# Rx_V2-2.net
KiCad netlist of a schematic drawn in EAGLE
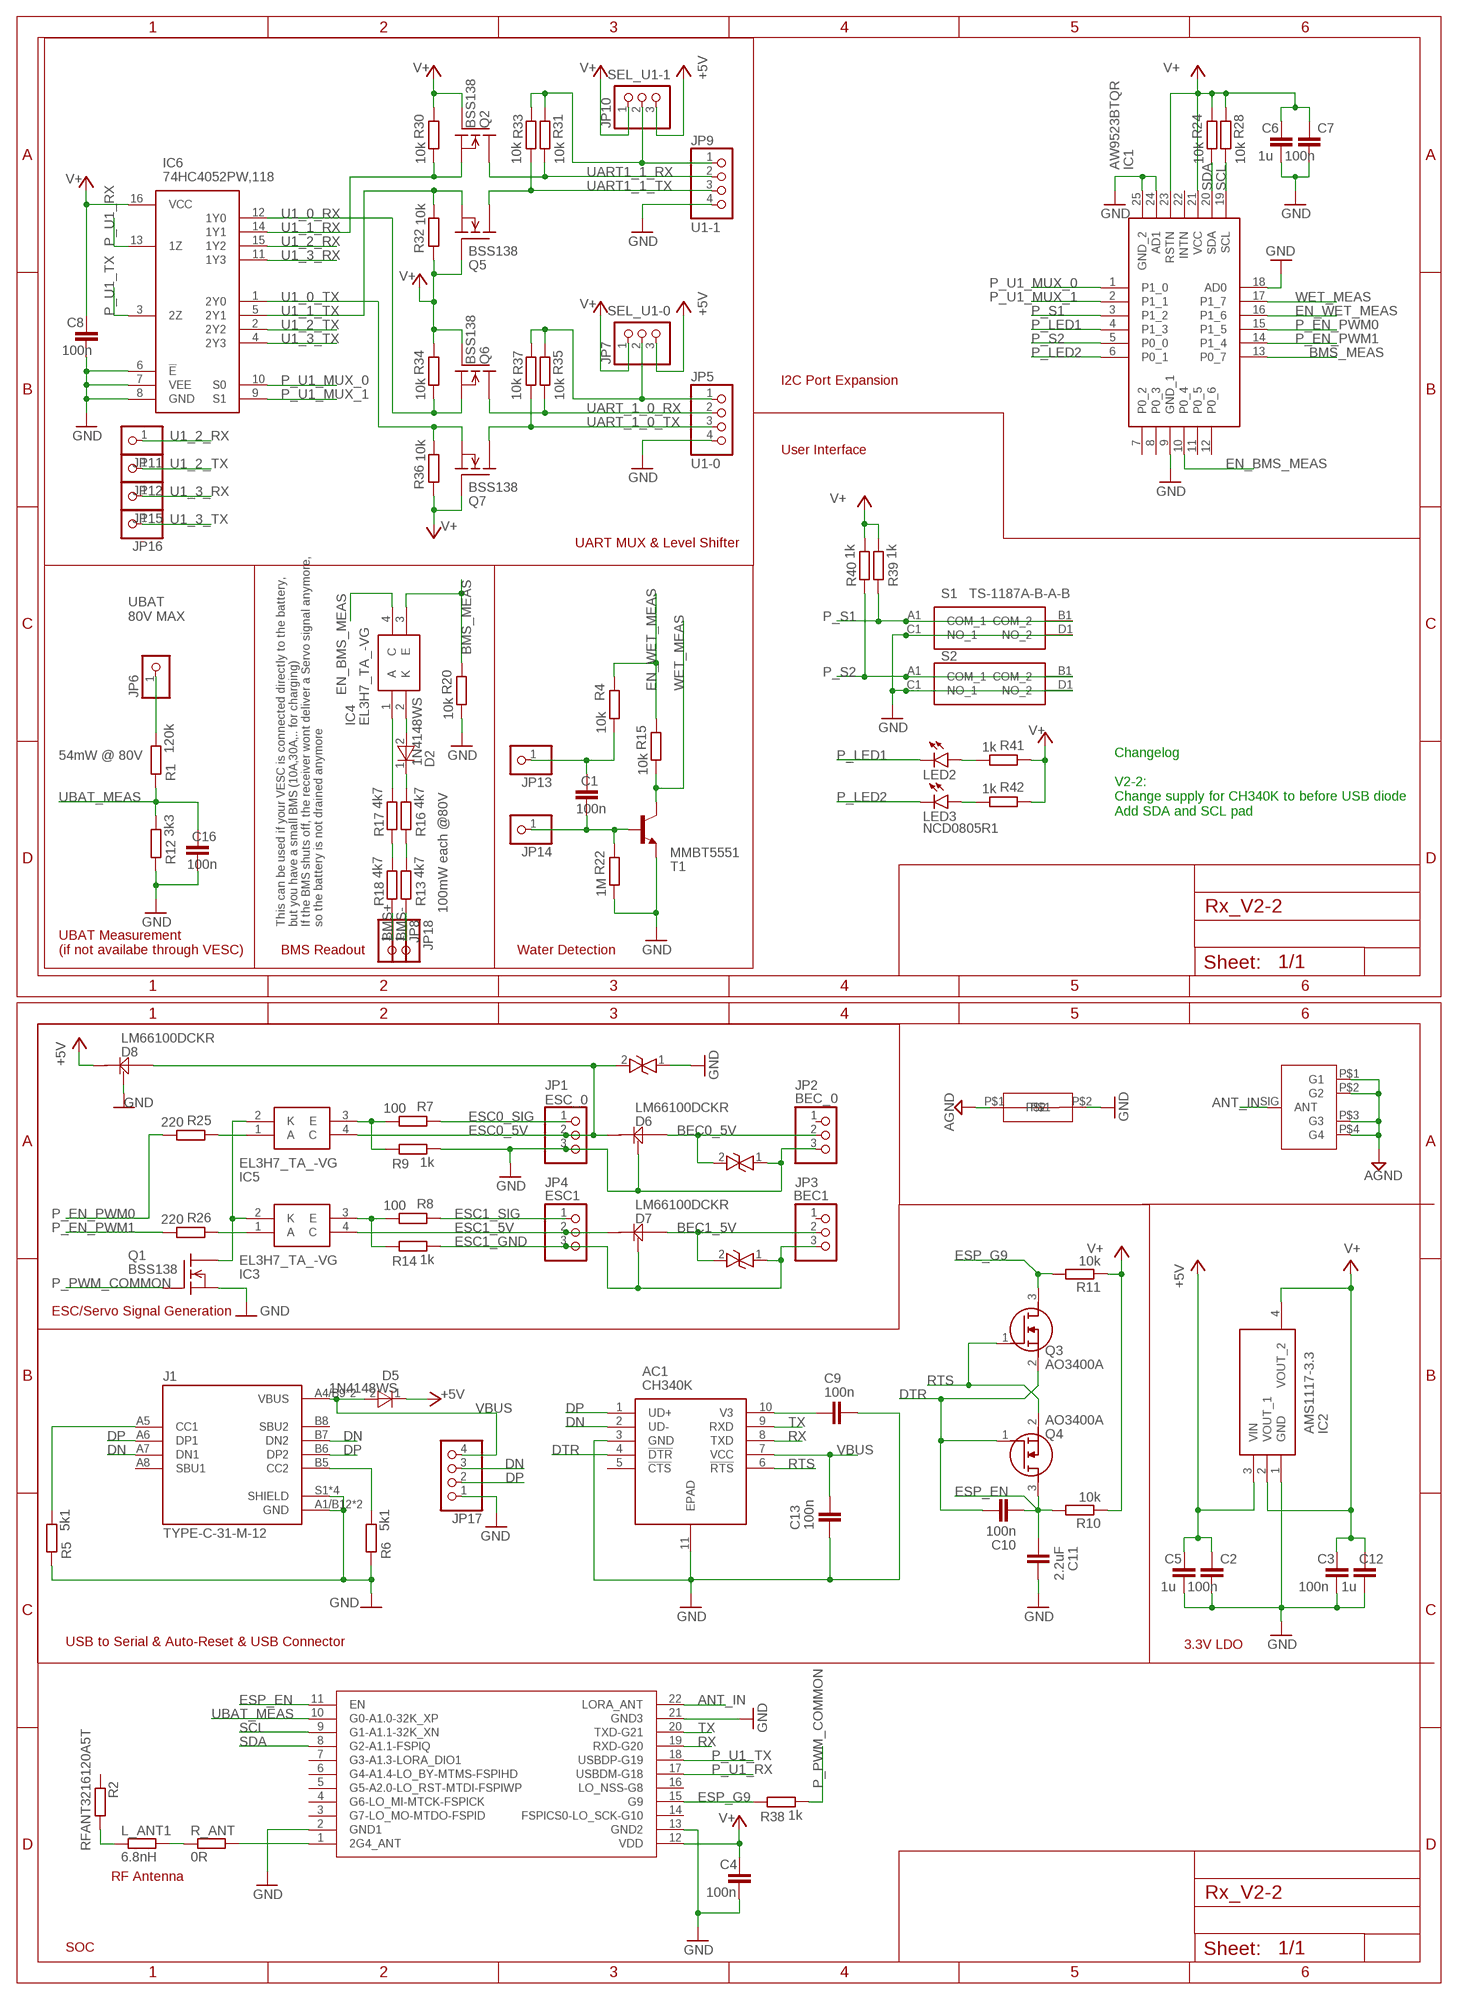
[diagram p0: schematic, sheet 1, part 1 of 2]
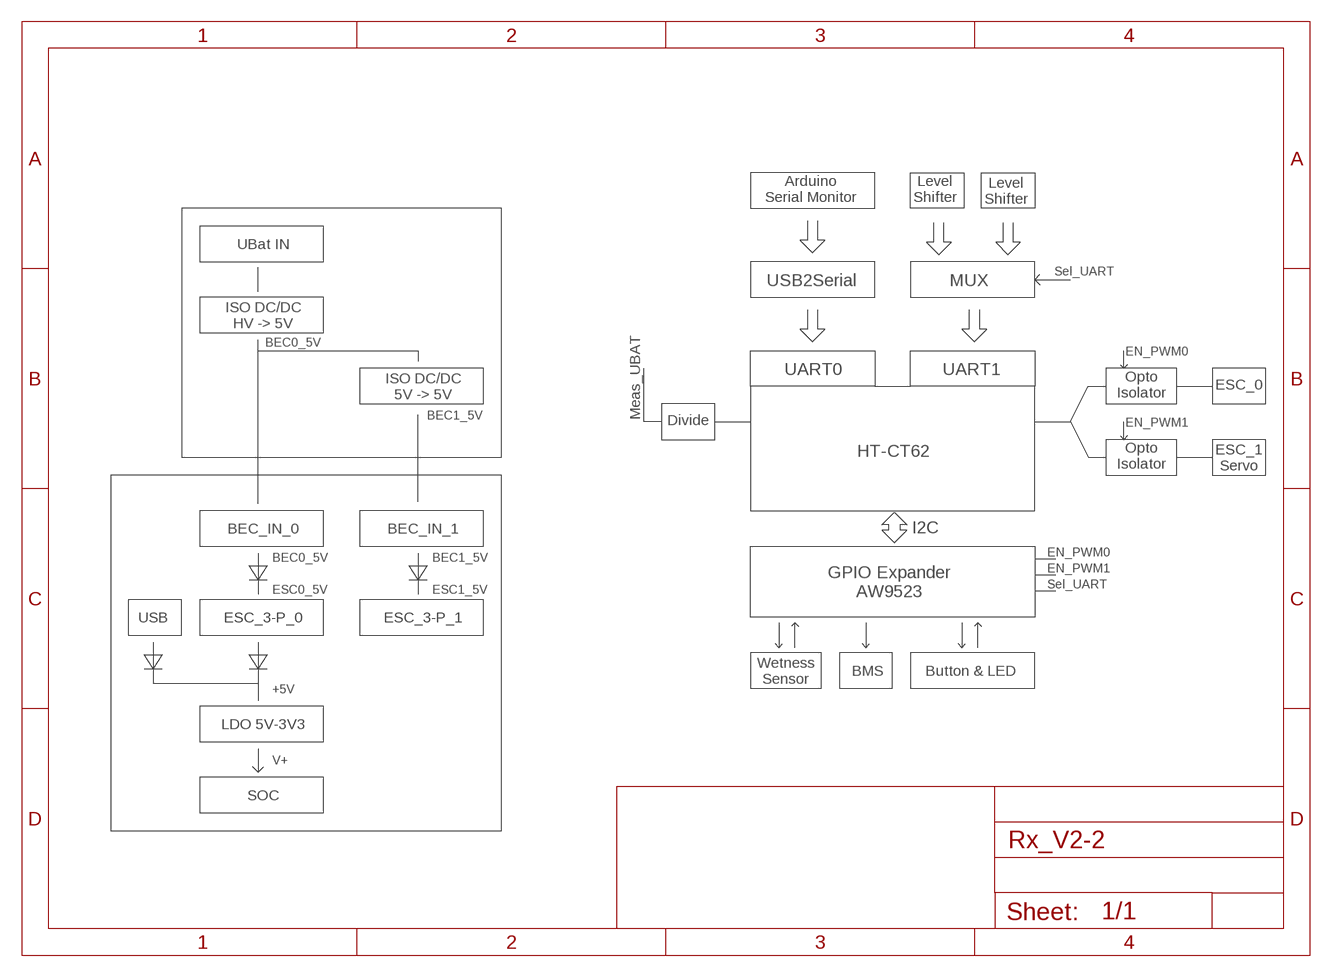
[diagram p1: schematic, sheet 1, part 2 of 2]

(export (version "E")
  (design (tool "Eeschema 10.0.6"))
  (components
    (comp (ref "AC1")
      (value "CH340K")
      (footprint "eagle-import:SOP100P600X180-11N")
      (libsource (lib "eagle-import") (part "CH340K"))
    )
    (comp (ref "C1")
      (value "100n")
      (footprint "eagle-import:C0603")
      (libsource (lib "eagle-import") (part "C-EUC0603"))
    )
    (comp (ref "C2")
      (value "100n")
      (footprint "eagle-import:C0603")
      (libsource (lib "eagle-import") (part "C-EUC0603"))
    )
    (comp (ref "C3")
      (value "100n")
      (footprint "eagle-import:C0603")
      (libsource (lib "eagle-import") (part "C-EUC0603"))
    )
    (comp (ref "C4")
      (value "100n")
      (footprint "eagle-import:C0603")
      (libsource (lib "eagle-import") (part "C-EUC0603"))
    )
    (comp (ref "C5")
      (value "1u")
      (footprint "eagle-import:C0603")
      (libsource (lib "eagle-import") (part "C-EUC0603"))
    )
    (comp (ref "C6")
      (value "1u")
      (footprint "eagle-import:C0603")
      (libsource (lib "eagle-import") (part "C-EUC0603"))
    )
    (comp (ref "C7")
      (value "100n")
      (footprint "eagle-import:C0603")
      (libsource (lib "eagle-import") (part "C-EUC0603"))
    )
    (comp (ref "C8")
      (value "100n")
      (footprint "eagle-import:C0603")
      (libsource (lib "eagle-import") (part "C-EUC0603"))
    )
    (comp (ref "C9")
      (value "100n")
      (footprint "eagle-import:C0603")
      (libsource (lib "eagle-import") (part "C-EUC0603"))
    )
    (comp (ref "C10")
      (value "100n")
      (footprint "eagle-import:C0603")
      (libsource (lib "eagle-import") (part "C-EUC0603"))
    )
    (comp (ref "C11")
      (value "2.2uF")
      (footprint "eagle-import:C0603")
      (libsource (lib "eagle-import") (part "C-EUC0603"))
    )
    (comp (ref "C12")
      (value "1u")
      (footprint "eagle-import:C0603")
      (libsource (lib "eagle-import") (part "C-EUC0603"))
    )
    (comp (ref "C13")
      (value "100n")
      (footprint "eagle-import:C0603")
      (libsource (lib "eagle-import") (part "C-EUC0603"))
    )
    (comp (ref "C16")
      (value "100n")
      (footprint "eagle-import:C0603")
      (libsource (lib "eagle-import") (part "C-EUC0603"))
    )
    (comp (ref "D1")
      (value "P6SMB6.8CA")
      (footprint "eagle-import:DIONM5436X261N")
      (fields (field (name "MOUSER_PART_NUMBER") "576-P6SMB6.8CA"))
      (libsource (lib "eagle-import") (part "P6SMB6.8CA"))
    )
    (comp (ref "D2")
      (value "1N4148WS")
      (footprint "eagle-import:SODFL2512X90N")
      (fields (field (name "MOUSER_PART_NUMBER") "512-1N4148WS"))
      (libsource (lib "eagle-import") (part "1N4148WS"))
    )
    (comp (ref "D3")
      (value "P6SMB6.8CA")
      (footprint "eagle-import:DIONM5436X261N")
      (fields (field (name "MOUSER_PART_NUMBER") "576-P6SMB6.8CA"))
      (libsource (lib "eagle-import") (part "P6SMB6.8CA"))
    )
    (comp (ref "D4")
      (value "P6SMB6.8CA")
      (footprint "eagle-import:DIONM5436X261N")
      (fields (field (name "MOUSER_PART_NUMBER") "576-P6SMB6.8CA"))
      (libsource (lib "eagle-import") (part "P6SMB6.8CA"))
    )
    (comp (ref "D5")
      (value "1N4148WS")
      (footprint "eagle-import:SODFL2512X90N")
      (fields (field (name "MOUSER_PART_NUMBER") "512-1N4148WS"))
      (libsource (lib "eagle-import") (part "1N4148WS"))
    )
    (comp (ref "D6")
      (value "LM66100DCKR")
      (footprint "eagle-import:SOP65P210X110-6N")
      (fields (field (name "MOUSER_PART_NUMBER") "595-LM66100DCKR"))
      (libsource (lib "eagle-import") (part "LM66100DCKR"))
    )
    (comp (ref "D7")
      (value "LM66100DCKR")
      (footprint "eagle-import:SOP65P210X110-6N")
      (fields (field (name "MOUSER_PART_NUMBER") "595-LM66100DCKR"))
      (libsource (lib "eagle-import") (part "LM66100DCKR"))
    )
    (comp (ref "D8")
      (value "LM66100DCKR")
      (footprint "eagle-import:SOP65P210X110-6N")
      (fields (field (name "MOUSER_PART_NUMBER") "595-LM66100DCKR"))
      (libsource (lib "eagle-import") (part "LM66100DCKR"))
    )
    (comp (ref "IC1")
      (value "AW9523BTQR")
      (footprint "eagle-import:QFN50P400X400X80-25N")
      (libsource (lib "eagle-import") (part "AW9523BTQR"))
    )
    (comp (ref "IC2")
      (value "AMS1117-3.3")
      (footprint "eagle-import:SOT229P700X180-4N")
      (libsource (lib "eagle-import") (part "AMS1117-3.3"))
    )
    (comp (ref "IC3")
      (value "EL3H7_TA_-VG")
      (footprint "eagle-import:SOIC127P700X200-4N")
      (fields
        (field (name "ARROW_PART_NUMBER") "EL3H7(TA)-VG")
        (field (name "MOUSER_PART_NUMBER") "638-EL3H7TAVG")
      )
      (libsource (lib "eagle-import") (part "EL3H7_TA_-VG"))
    )
    (comp (ref "IC4")
      (value "EL3H7_TA_-VG")
      (footprint "eagle-import:SOIC127P700X200-4N")
      (fields
        (field (name "ARROW_PART_NUMBER") "EL3H7(TA)-VG")
        (field (name "MOUSER_PART_NUMBER") "638-EL3H7TAVG")
      )
      (libsource (lib "eagle-import") (part "EL3H7_TA_-VG"))
    )
    (comp (ref "IC5")
      (value "EL3H7_TA_-VG")
      (footprint "eagle-import:SOIC127P700X200-4N")
      (fields
        (field (name "ARROW_PART_NUMBER") "EL3H7(TA)-VG")
        (field (name "MOUSER_PART_NUMBER") "638-EL3H7TAVG")
      )
      (libsource (lib "eagle-import") (part "EL3H7_TA_-VG"))
    )
    (comp (ref "IC6")
      (value "74HC4052PW,118")
      (footprint "eagle-import:SOP65P640X110-16N")
      (fields (field (name "MOUSER_PART_NUMBER") "771-74HC4052PW-T"))
      (libsource (lib "eagle-import") (part "74HC4052PW,118"))
    )
    (comp (ref "J1")
      (value "TYPE-C-31-M-12")
      (footprint "eagle-import:HRO_TYPE-C-31-M-12")
      (fields (field (name "MF") "HRO Electronics Co., Ltd."))
      (libsource (lib "eagle-import") (part "TYPE-C-31-M-12"))
    )
    (comp (ref "JP1")
      (value "ESC_0")
      (footprint "eagle-import:1X03")
      (libsource (lib "eagle-import") (part "PINHD-1X3"))
    )
    (comp (ref "JP2")
      (value "BEC_0")
      (footprint "eagle-import:1X03")
      (libsource (lib "eagle-import") (part "PINHD-1X3"))
    )
    (comp (ref "JP3")
      (value "BEC1")
      (footprint "eagle-import:1X03")
      (libsource (lib "eagle-import") (part "PINHD-1X3"))
    )
    (comp (ref "JP4")
      (value "ESC1")
      (footprint "eagle-import:1X03")
      (libsource (lib "eagle-import") (part "PINHD-1X3"))
    )
    (comp (ref "JP5")
      (value "U1-0")
      (footprint "eagle-import:1X04")
      (libsource (lib "eagle-import") (part "PINHD-1X4"))
    )
    (comp (ref "JP6")
      (value "PINHD-1X1")
      (footprint "eagle-import:1X01")
      (libsource (lib "eagle-import") (part "PINHD-1X1"))
    )
    (comp (ref "JP7")
      (value "SEL_U1-0")
      (footprint "eagle-import:1X03")
      (libsource (lib "eagle-import") (part "PINHD-1X3"))
    )
    (comp (ref "JP8")
      (value "PINHD-1X1")
      (footprint "eagle-import:1X01")
      (libsource (lib "eagle-import") (part "PINHD-1X1"))
    )
    (comp (ref "JP9")
      (value "U1-1")
      (footprint "eagle-import:1X04")
      (libsource (lib "eagle-import") (part "PINHD-1X4"))
    )
    (comp (ref "JP10")
      (value "SEL_U1-1")
      (footprint "eagle-import:1X03")
      (libsource (lib "eagle-import") (part "PINHD-1X3"))
    )
    (comp (ref "JP11")
      (value "PINHD-1X1")
      (footprint "eagle-import:1X01")
      (libsource (lib "eagle-import") (part "PINHD-1X1"))
    )
    (comp (ref "JP12")
      (value "PINHD-1X1")
      (footprint "eagle-import:1X01")
      (libsource (lib "eagle-import") (part "PINHD-1X1"))
    )
    (comp (ref "JP13")
      (value "PINHD-1X1")
      (footprint "eagle-import:1X01")
      (libsource (lib "eagle-import") (part "PINHD-1X1"))
    )
    (comp (ref "JP14")
      (value "PINHD-1X1")
      (footprint "eagle-import:1X01")
      (libsource (lib "eagle-import") (part "PINHD-1X1"))
    )
    (comp (ref "JP15")
      (value "PINHD-1X1")
      (footprint "eagle-import:1X01")
      (libsource (lib "eagle-import") (part "PINHD-1X1"))
    )
    (comp (ref "JP16")
      (value "PINHD-1X1")
      (footprint "eagle-import:1X01")
      (libsource (lib "eagle-import") (part "PINHD-1X1"))
    )
    (comp (ref "JP17")
      (value "PINHD-1X4")
      (footprint "eagle-import:1X04")
      (libsource (lib "eagle-import") (part "PINHD-1X4"))
    )
    (comp (ref "JP18")
      (value "PINHD-1X1")
      (footprint "eagle-import:1X01")
      (libsource (lib "eagle-import") (part "PINHD-1X1"))
    )
    (comp (ref "LED2")
      (value "NCD0805R1")
      (footprint "eagle-import:CHIP-LED0805")
      (libsource (lib "eagle-import") (part "LEDCHIP-LED0805"))
    )
    (comp (ref "LED3")
      (value "NCD0805R1")
      (footprint "eagle-import:CHIP-LED0805")
      (libsource (lib "eagle-import") (part "LEDCHIP-LED0805"))
    )
    (comp (ref "L_ANT1")
      (value "6.8nH")
      (footprint "eagle-import:R0402")
      (libsource (lib "eagle-import") (part "R-EU_R0402"))
    )
    (comp (ref "Q1")
      (value "BSS138")
      (footprint "eagle-import:SOT23")
      (libsource (lib "eagle-import") (part "BSS138"))
    )
    (comp (ref "Q2")
      (value "BSS138")
      (footprint "eagle-import:SOT23")
      (libsource (lib "eagle-import") (part "BSS138"))
    )
    (comp (ref "Q3")
      (value "AO3400A")
      (footprint "eagle-import:SOT95P280X125-3N")
      (libsource (lib "eagle-import") (part "AO3400A"))
    )
    (comp (ref "Q4")
      (value "AO3400A")
      (footprint "eagle-import:SOT95P280X125-3N")
      (libsource (lib "eagle-import") (part "AO3400A"))
    )
    (comp (ref "Q5")
      (value "BSS138")
      (footprint "eagle-import:SOT23")
      (libsource (lib "eagle-import") (part "BSS138"))
    )
    (comp (ref "Q6")
      (value "BSS138")
      (footprint "eagle-import:SOT23")
      (libsource (lib "eagle-import") (part "BSS138"))
    )
    (comp (ref "Q7")
      (value "BSS138")
      (footprint "eagle-import:SOT23")
      (libsource (lib "eagle-import") (part "BSS138"))
    )
    (comp (ref "R1")
      (value "120k")
      (footprint "eagle-import:R0603")
      (libsource (lib "eagle-import") (part "R-EU_R0603"))
    )
    (comp (ref "R2")
      (value "RFANT3216120A5T")
      (footprint "eagle-import:R1206")
      (libsource (lib "eagle-import") (part "R-EU_R1206"))
    )
    (comp (ref "R4")
      (value "10k")
      (footprint "eagle-import:R0603")
      (libsource (lib "eagle-import") (part "R-EU_R0603"))
    )
    (comp (ref "R5")
      (value "5k1")
      (footprint "eagle-import:R0603")
      (libsource (lib "eagle-import") (part "R-EU_R0603"))
    )
    (comp (ref "R6")
      (value "5k1")
      (footprint "eagle-import:R0603")
      (libsource (lib "eagle-import") (part "R-EU_R0603"))
    )
    (comp (ref "R7")
      (value "100")
      (footprint "eagle-import:R0603")
      (libsource (lib "eagle-import") (part "R-EU_R0603"))
    )
    (comp (ref "R8")
      (value "100")
      (footprint "eagle-import:R0603")
      (libsource (lib "eagle-import") (part "R-EU_R0603"))
    )
    (comp (ref "R9")
      (value "1k")
      (footprint "eagle-import:R0603")
      (libsource (lib "eagle-import") (part "R-EU_R0603"))
    )
    (comp (ref "R10")
      (value "10k")
      (footprint "eagle-import:R0603")
      (libsource (lib "eagle-import") (part "R-EU_R0603"))
    )
    (comp (ref "R11")
      (value "10k")
      (footprint "eagle-import:R0603")
      (libsource (lib "eagle-import") (part "R-EU_R0603"))
    )
    (comp (ref "R12")
      (value "3k3")
      (footprint "eagle-import:R0603")
      (libsource (lib "eagle-import") (part "R-EU_R0603"))
    )
    (comp (ref "R13")
      (value "4k7")
      (footprint "eagle-import:R0603")
      (libsource (lib "eagle-import") (part "R-EU_R0603"))
    )
    (comp (ref "R14")
      (value "1k")
      (footprint "eagle-import:R0603")
      (libsource (lib "eagle-import") (part "R-EU_R0603"))
    )
    (comp (ref "R15")
      (value "10k")
      (footprint "eagle-import:R0603")
      (libsource (lib "eagle-import") (part "R-EU_R0603"))
    )
    (comp (ref "R16")
      (value "4k7")
      (footprint "eagle-import:R0603")
      (libsource (lib "eagle-import") (part "R-EU_R0603"))
    )
    (comp (ref "R17")
      (value "4k7")
      (footprint "eagle-import:R0603")
      (libsource (lib "eagle-import") (part "R-EU_R0603"))
    )
    (comp (ref "R18")
      (value "4k7")
      (footprint "eagle-import:R0603")
      (libsource (lib "eagle-import") (part "R-EU_R0603"))
    )
    (comp (ref "R20")
      (value "10k")
      (footprint "eagle-import:R0603")
      (libsource (lib "eagle-import") (part "R-EU_R0603"))
    )
    (comp (ref "R22")
      (value "1M")
      (footprint "eagle-import:R0603")
      (libsource (lib "eagle-import") (part "R-EU_R0603"))
    )
    (comp (ref "R24")
      (value "10k")
      (footprint "eagle-import:R0603")
      (libsource (lib "eagle-import") (part "R-EU_R0603"))
    )
    (comp (ref "R25")
      (value "220")
      (footprint "eagle-import:R0603")
      (libsource (lib "eagle-import") (part "R-EU_R0603"))
    )
    (comp (ref "R26")
      (value "220")
      (footprint "eagle-import:R0603")
      (libsource (lib "eagle-import") (part "R-EU_R0603"))
    )
    (comp (ref "R28")
      (value "10k")
      (footprint "eagle-import:R0603")
      (libsource (lib "eagle-import") (part "R-EU_R0603"))
    )
    (comp (ref "R30")
      (value "10k")
      (footprint "eagle-import:R0603")
      (libsource (lib "eagle-import") (part "R-EU_R0603"))
    )
    (comp (ref "R31")
      (value "10k")
      (footprint "eagle-import:R0603")
      (libsource (lib "eagle-import") (part "R-EU_R0603"))
    )
    (comp (ref "R32")
      (value "10k")
      (footprint "eagle-import:R0603")
      (libsource (lib "eagle-import") (part "R-EU_R0603"))
    )
    (comp (ref "R33")
      (value "10k")
      (footprint "eagle-import:R0603")
      (libsource (lib "eagle-import") (part "R-EU_R0603"))
    )
    (comp (ref "R34")
      (value "10k")
      (footprint "eagle-import:R0603")
      (libsource (lib "eagle-import") (part "R-EU_R0603"))
    )
    (comp (ref "R35")
      (value "10k")
      (footprint "eagle-import:R0603")
      (libsource (lib "eagle-import") (part "R-EU_R0603"))
    )
    (comp (ref "R36")
      (value "10k")
      (footprint "eagle-import:R0603")
      (libsource (lib "eagle-import") (part "R-EU_R0603"))
    )
    (comp (ref "R37")
      (value "10k")
      (footprint "eagle-import:R0603")
      (libsource (lib "eagle-import") (part "R-EU_R0603"))
    )
    (comp (ref "R38")
      (value "1k")
      (footprint "eagle-import:R0603")
      (libsource (lib "eagle-import") (part "R-EU_R0603"))
    )
    (comp (ref "R39")
      (value "1k")
      (footprint "eagle-import:R0603")
      (libsource (lib "eagle-import") (part "R-EU_R0603"))
    )
    (comp (ref "R40")
      (value "1k")
      (footprint "eagle-import:R0603")
      (libsource (lib "eagle-import") (part "R-EU_R0603"))
    )
    (comp (ref "R41")
      (value "1k")
      (footprint "eagle-import:R0603")
      (libsource (lib "eagle-import") (part "R-EU_R0603"))
    )
    (comp (ref "R42")
      (value "1k")
      (footprint "eagle-import:R0603")
      (libsource (lib "eagle-import") (part "R-EU_R0603"))
    )
    (comp (ref "R_ANT")
      (value "0R")
      (footprint "eagle-import:R0402")
      (libsource (lib "eagle-import") (part "R-EU_R0402"))
    )
    (comp (ref "S1")
      (value "TS-1187A-B-A-B")
      (footprint "eagle-import:TS1187ABAB")
      (libsource (lib "eagle-import") (part "TS-1187A-B-A-B"))
    )
    (comp (ref "S2")
      (value "TS-1187A-B-A-B")
      (footprint "eagle-import:TS1187ABAB")
      (libsource (lib "eagle-import") (part "TS-1187A-B-A-B"))
    )
    (comp (ref "T1")
      (value "MMBT5551")
      (footprint "eagle-import:SOT23-BEC")
      (libsource (lib "eagle-import") (part "-NPN-SOT23-BECBC847B"))
    )
    (comp (ref "U$1")
      (value "SMA_5.08_1.4")
      (footprint "eagle-import:SMA_5.08_1.4")
      (libsource (lib "eagle-import") (part "SMA_5.08_1.4"))
    )
    (comp (ref "U$5")
      (value "HT-CT62")
      (footprint "eagle-import:HT-CT62")
      (libsource (lib "eagle-import") (part "HT-CT62"))
    )
    (comp (ref "U$7")
      (value "NETTIE_0.6MM")
      (footprint "eagle-import:0.6MM")
      (libsource (lib "eagle-import") (part "NETTIE_0.6MM"))
    )
  )
  (nets
    (net (code "1") (name "+5V") (class "Default")
      (node (ref "C2") (pin "1") (pinfunction "1_1") (pintype "passive"))
      (node (ref "C5") (pin "1") (pinfunction "1_1") (pintype "passive"))
      (node (ref "D5") (pin "1") (pinfunction "K_1") (pintype "bidirectional"))
      (node (ref "D8") (pin "3") (pinfunction "VOUT_3") (pintype "bidirectional"))
      (node (ref "D8") (pin "6") (pinfunction "VOUT_6") (pintype "bidirectional"))
      (node (ref "IC2") (pin "3") (pinfunction "VIN_3") (pintype "bidirectional"))
      (node (ref "JP10") (pin "3") (pinfunction "3_3") (pintype "passive"))
      (node (ref "JP7") (pin "3") (pinfunction "3_3") (pintype "passive"))
    )
    (net (code "2") (name "/ANT_IN") (class "Default")
      (node (ref "U$1") (pin "SIG") (pinfunction "ANT_SIG") (pintype "bidirectional"))
      (node (ref "U$5") (pin "22") (pinfunction "LORA_ANT_22") (pintype "bidirectional"))
    )
    (net (code "3") (name "/BEC0_5V") (class "Default")
      (node (ref "D1") (pin "2") (pinfunction "2_2") (pintype "bidirectional"))
      (node (ref "D6") (pin "1") (pinfunction "VIN_1") (pintype "bidirectional"))
      (node (ref "JP2") (pin "2") (pinfunction "2_2") (pintype "passive"))
    )
    (net (code "4") (name "/BEC1_5V") (class "Default")
      (node (ref "D3") (pin "2") (pinfunction "2_2") (pintype "bidirectional"))
      (node (ref "D7") (pin "1") (pinfunction "VIN_1") (pintype "bidirectional"))
      (node (ref "JP3") (pin "2") (pinfunction "2_2") (pintype "passive"))
    )
    (net (code "5") (name "/BMS+") (class "Default")
      (node (ref "JP8") (pin "1") (pinfunction "1_1") (pintype "passive"))
      (node (ref "R18") (pin "1") (pinfunction "1_1") (pintype "passive"))
    )
    (net (code "6") (name "/BMS-") (class "Default")
      (node (ref "JP18") (pin "1") (pinfunction "1_1") (pintype "passive"))
      (node (ref "R13") (pin "1") (pinfunction "1_1") (pintype "passive"))
    )
    (net (code "7") (name "/BMS_MEAS") (class "Default")
      (node (ref "IC1") (pin "13") (pinfunction "P0_7_13") (pintype "bidirectional"))
      (node (ref "IC4") (pin "3") (pinfunction "E_3") (pintype "bidirectional"))
      (node (ref "R20") (pin "1") (pinfunction "1_1") (pintype "passive"))
    )
    (net (code "8") (name "/DN") (class "Default")
      (node (ref "AC1") (pin "2") (pinfunction "UD-_2") (pintype "bidirectional"))
      (node (ref "J1") (pin "A7") (pinfunction "DN1_A7") (pintype "bidirectional"))
      (node (ref "J1") (pin "B7") (pinfunction "DN2_B7") (pintype "bidirectional"))
      (node (ref "JP17") (pin "3") (pinfunction "3_3") (pintype "passive"))
    )
    (net (code "9") (name "/DP") (class "Default")
      (node (ref "AC1") (pin "1") (pinfunction "UD+_1") (pintype "bidirectional"))
      (node (ref "J1") (pin "A6") (pinfunction "DP1_A6") (pintype "bidirectional"))
      (node (ref "J1") (pin "B6") (pinfunction "DP2_B6") (pintype "bidirectional"))
      (node (ref "JP17") (pin "2") (pinfunction "2_2") (pintype "passive"))
    )
    (net (code "10") (name "/DTR") (class "Default")
      (node (ref "AC1") (pin "4") (pinfunction "~{DTR}_4") (pintype "bidirectional"))
      (node (ref "C10") (pin "1") (pinfunction "1_1") (pintype "passive"))
      (node (ref "Q3") (pin "2") (pinfunction "S_2") (pintype "bidirectional"))
      (node (ref "Q4") (pin "1") (pinfunction "G_1") (pintype "bidirectional"))
    )
    (net (code "11") (name "/EN_BMS_MEAS") (class "Default")
      (node (ref "IC1") (pin "10") (pinfunction "P0_4_10") (pintype "bidirectional"))
      (node (ref "IC4") (pin "4") (pinfunction "C_4") (pintype "bidirectional"))
    )
    (net (code "12") (name "/EN_WET_MEAS") (class "Default")
      (node (ref "IC1") (pin "16") (pinfunction "P1_6_16") (pintype "bidirectional"))
      (node (ref "R15") (pin "1") (pinfunction "1_1") (pintype "passive"))
      (node (ref "R4") (pin "1") (pinfunction "1_1") (pintype "passive"))
    )
    (net (code "13") (name "/ESC0_5V") (class "Default")
      (node (ref "D4") (pin "2") (pinfunction "2_2") (pintype "bidirectional"))
      (node (ref "D6") (pin "3") (pinfunction "VOUT_3") (pintype "bidirectional"))
      (node (ref "D6") (pin "6") (pinfunction "VOUT_6") (pintype "bidirectional"))
      (node (ref "D8") (pin "1") (pinfunction "VIN_1") (pintype "bidirectional"))
      (node (ref "IC5") (pin "4") (pinfunction "C_4") (pintype "bidirectional"))
      (node (ref "JP1") (pin "2") (pinfunction "2_2") (pintype "passive"))
    )
    (net (code "14") (name "/ESC0_SIG") (class "Default")
      (node (ref "JP1") (pin "1") (pinfunction "1_1") (pintype "passive"))
      (node (ref "R7") (pin "1") (pinfunction "1_1") (pintype "passive"))
    )
    (net (code "15") (name "/ESC1_5V") (class "Default")
      (node (ref "D7") (pin "3") (pinfunction "VOUT_3") (pintype "bidirectional"))
      (node (ref "D7") (pin "6") (pinfunction "VOUT_6") (pintype "bidirectional"))
      (node (ref "IC3") (pin "4") (pinfunction "C_4") (pintype "bidirectional"))
      (node (ref "JP4") (pin "2") (pinfunction "2_2") (pintype "passive"))
    )
    (net (code "16") (name "/ESC1_GND") (class "Default")
      (node (ref "D3") (pin "1") (pinfunction "1_1") (pintype "bidirectional"))
      (node (ref "D7") (pin "2") (pinfunction "GND_2") (pintype "bidirectional"))
      (node (ref "D7") (pin "4") (pinfunction "GND_4") (pintype "bidirectional"))
      (node (ref "D7") (pin "5") (pinfunction "GND_5") (pintype "bidirectional"))
      (node (ref "JP3") (pin "3") (pinfunction "3_3") (pintype "passive"))
      (node (ref "JP4") (pin "3") (pinfunction "3_3") (pintype "passive"))
      (node (ref "R14") (pin "2") (pinfunction "2_2") (pintype "passive"))
    )
    (net (code "17") (name "/ESC1_SIG") (class "Default")
      (node (ref "JP4") (pin "1") (pinfunction "1_1") (pintype "passive"))
      (node (ref "R8") (pin "1") (pinfunction "1_1") (pintype "passive"))
    )
    (net (code "18") (name "/ESP_EN") (class "Default")
      (node (ref "C10") (pin "2") (pinfunction "2_2") (pintype "passive"))
      (node (ref "C11") (pin "2") (pinfunction "2_2") (pintype "passive"))
      (node (ref "Q4") (pin "3") (pinfunction "D_3") (pintype "bidirectional"))
      (node (ref "R10") (pin "2") (pinfunction "2_2") (pintype "passive"))
      (node (ref "U$5") (pin "11") (pinfunction "EN_11") (pintype "bidirectional"))
    )
    (net (code "19") (name "/ESP_G9") (class "Default")
      (node (ref "Q3") (pin "3") (pinfunction "D_3") (pintype "bidirectional"))
      (node (ref "R11") (pin "2") (pinfunction "2_2") (pintype "passive"))
      (node (ref "R38") (pin "1") (pinfunction "1_1") (pintype "passive"))
      (node (ref "U$5") (pin "15") (pinfunction "G9_15") (pintype "bidirectional"))
    )
    (net (code "20") (name "/P_EN_PWM0") (class "Default")
      (node (ref "IC1") (pin "15") (pinfunction "P1_5_15") (pintype "bidirectional"))
      (node (ref "R25") (pin "2") (pinfunction "2_2") (pintype "passive"))
    )
    (net (code "21") (name "/P_EN_PWM1") (class "Default")
      (node (ref "IC1") (pin "14") (pinfunction "P1_4_14") (pintype "bidirectional"))
      (node (ref "R26") (pin "2") (pinfunction "2_2") (pintype "passive"))
    )
    (net (code "22") (name "/P_LED1") (class "Default")
      (node (ref "IC1") (pin "4") (pinfunction "P1_3_4") (pintype "bidirectional"))
      (node (ref "LED2") (pin "C") (pinfunction "C_C") (pintype "passive"))
    )
    (net (code "23") (name "/P_LED2") (class "Default")
      (node (ref "IC1") (pin "6") (pinfunction "P0_1_6") (pintype "bidirectional"))
      (node (ref "LED3") (pin "C") (pinfunction "C_C") (pintype "passive"))
    )
    (net (code "24") (name "/P_PWM_COMMON") (class "Default")
      (node (ref "Q1") (pin "1") (pinfunction "G_1") (pintype "passive"))
      (node (ref "R38") (pin "2") (pinfunction "2_2") (pintype "passive"))
    )
    (net (code "25") (name "/P_S1") (class "Default")
      (node (ref "IC1") (pin "3") (pinfunction "P1_2_3") (pintype "bidirectional"))
      (node (ref "R39") (pin "1") (pinfunction "1_1") (pintype "passive"))
      (node (ref "S1") (pin "A1") (pinfunction "COM_1_A1") (pintype "bidirectional"))
      (node (ref "S1") (pin "B1") (pinfunction "COM_2_B1") (pintype "bidirectional"))
    )
    (net (code "26") (name "/P_S2") (class "Default")
      (node (ref "IC1") (pin "5") (pinfunction "P0_0_5") (pintype "bidirectional"))
      (node (ref "R40") (pin "1") (pinfunction "1_1") (pintype "passive"))
      (node (ref "S2") (pin "A1") (pinfunction "COM_1_A1") (pintype "bidirectional"))
      (node (ref "S2") (pin "B1") (pinfunction "COM_2_B1") (pintype "bidirectional"))
    )
    (net (code "27") (name "/P_U1_MUX_0") (class "Default")
      (node (ref "IC1") (pin "1") (pinfunction "P1_0_1") (pintype "bidirectional"))
      (node (ref "IC6") (pin "10") (pinfunction "S0_10") (pintype "bidirectional"))
    )
    (net (code "28") (name "/P_U1_MUX_1") (class "Default")
      (node (ref "IC1") (pin "2") (pinfunction "P1_1_2") (pintype "bidirectional"))
      (node (ref "IC6") (pin "9") (pinfunction "S1_9") (pintype "bidirectional"))
    )
    (net (code "29") (name "/P_U1_RX") (class "Default")
      (node (ref "IC6") (pin "13") (pinfunction "1Z_13") (pintype "bidirectional"))
      (node (ref "U$5") (pin "17") (pinfunction "USBDM-G18_17") (pintype "bidirectional"))
    )
    (net (code "30") (name "/P_U1_TX") (class "Default")
      (node (ref "IC6") (pin "3") (pinfunction "2Z_3") (pintype "bidirectional"))
      (node (ref "U$5") (pin "18") (pinfunction "USBDP-G19_18") (pintype "bidirectional"))
    )
    (net (code "31") (name "/RTS") (class "Default")
      (node (ref "AC1") (pin "6") (pinfunction "~{RTS}_6") (pintype "bidirectional"))
      (node (ref "Q3") (pin "1") (pinfunction "G_1") (pintype "bidirectional"))
      (node (ref "Q4") (pin "2") (pinfunction "S_2") (pintype "bidirectional"))
    )
    (net (code "32") (name "/RX") (class "Default")
      (node (ref "AC1") (pin "8") (pinfunction "TXD_8") (pintype "bidirectional"))
      (node (ref "U$5") (pin "19") (pinfunction "RXD-G20_19") (pintype "bidirectional"))
    )
    (net (code "33") (name "/SCL") (class "Default")
      (node (ref "IC1") (pin "19") (pinfunction "SCL_19") (pintype "bidirectional"))
      (node (ref "R28") (pin "2") (pinfunction "2_2") (pintype "passive"))
      (node (ref "U$5") (pin "9") (pinfunction "G1-A1.1-32K_XN_9") (pintype "bidirectional"))
    )
    (net (code "34") (name "/SDA") (class "Default")
      (node (ref "IC1") (pin "20") (pinfunction "SDA_20") (pintype "bidirectional"))
      (node (ref "R24") (pin "2") (pinfunction "2_2") (pintype "passive"))
      (node (ref "U$5") (pin "8") (pinfunction "G2-A1.1-FSPIQ_8") (pintype "bidirectional"))
    )
    (net (code "35") (name "/TX") (class "Default")
      (node (ref "AC1") (pin "9") (pinfunction "RXD_9") (pintype "bidirectional"))
      (node (ref "U$5") (pin "20") (pinfunction "TXD-G21_20") (pintype "bidirectional"))
    )
    (net (code "36") (name "/U1_0_RX") (class "Default")
      (node (ref "IC6") (pin "12") (pinfunction "1Y0_12") (pintype "bidirectional"))
      (node (ref "Q6") (pin "2") (pinfunction "S_2") (pintype "passive"))
      (node (ref "R34") (pin "2") (pinfunction "2_2") (pintype "passive"))
    )
    (net (code "37") (name "/U1_0_TX") (class "Default")
      (node (ref "IC6") (pin "1") (pinfunction "2Y0_1") (pintype "bidirectional"))
      (node (ref "Q7") (pin "2") (pinfunction "S_2") (pintype "passive"))
      (node (ref "R36") (pin "2") (pinfunction "2_2") (pintype "passive"))
    )
    (net (code "38") (name "/U1_1_RX") (class "Default")
      (node (ref "IC6") (pin "14") (pinfunction "1Y1_14") (pintype "bidirectional"))
      (node (ref "Q2") (pin "2") (pinfunction "S_2") (pintype "passive"))
      (node (ref "R30") (pin "2") (pinfunction "2_2") (pintype "passive"))
    )
    (net (code "39") (name "/U1_1_TX") (class "Default")
      (node (ref "IC6") (pin "5") (pinfunction "2Y1_5") (pintype "bidirectional"))
      (node (ref "Q5") (pin "2") (pinfunction "S_2") (pintype "passive"))
      (node (ref "R32") (pin "2") (pinfunction "2_2") (pintype "passive"))
    )
    (net (code "40") (name "/U1_2_RX") (class "Default")
      (node (ref "IC6") (pin "15") (pinfunction "1Y2_15") (pintype "bidirectional"))
      (node (ref "JP11") (pin "1") (pinfunction "1_1") (pintype "passive"))
    )
    (net (code "41") (name "/U1_2_TX") (class "Default")
      (node (ref "IC6") (pin "2") (pinfunction "2Y2_2") (pintype "bidirectional"))
      (node (ref "JP12") (pin "1") (pinfunction "1_1") (pintype "passive"))
    )
    (net (code "42") (name "/U1_3_RX") (class "Default")
      (node (ref "IC6") (pin "11") (pinfunction "1Y3_11") (pintype "bidirectional"))
      (node (ref "JP15") (pin "1") (pinfunction "1_1") (pintype "passive"))
    )
    (net (code "43") (name "/U1_3_TX") (class "Default")
      (node (ref "IC6") (pin "4") (pinfunction "2Y3_4") (pintype "bidirectional"))
      (node (ref "JP16") (pin "1") (pinfunction "1_1") (pintype "passive"))
    )
    (net (code "44") (name "/UART1_1_RX") (class "Default")
      (node (ref "JP9") (pin "2") (pinfunction "2_2") (pintype "passive"))
      (node (ref "Q2") (pin "3") (pinfunction "D_3") (pintype "passive"))
      (node (ref "R31") (pin "2") (pinfunction "2_2") (pintype "passive"))
    )
    (net (code "45") (name "/UART1_1_TX") (class "Default")
      (node (ref "JP9") (pin "3") (pinfunction "3_3") (pintype "passive"))
      (node (ref "Q5") (pin "3") (pinfunction "D_3") (pintype "passive"))
      (node (ref "R33") (pin "2") (pinfunction "2_2") (pintype "passive"))
    )
    (net (code "46") (name "/UART_1_0_RX") (class "Default")
      (node (ref "JP5") (pin "2") (pinfunction "2_2") (pintype "passive"))
      (node (ref "Q6") (pin "3") (pinfunction "D_3") (pintype "passive"))
      (node (ref "R35") (pin "2") (pinfunction "2_2") (pintype "passive"))
    )
    (net (code "47") (name "/UART_1_0_TX") (class "Default")
      (node (ref "JP5") (pin "3") (pinfunction "3_3") (pintype "passive"))
      (node (ref "Q7") (pin "3") (pinfunction "D_3") (pintype "passive"))
      (node (ref "R37") (pin "2") (pinfunction "2_2") (pintype "passive"))
    )
    (net (code "48") (name "/UBAT_MEAS") (class "Default")
      (node (ref "C16") (pin "1") (pinfunction "1_1") (pintype "passive"))
      (node (ref "R1") (pin "1") (pinfunction "1_1") (pintype "passive"))
      (node (ref "R12") (pin "2") (pinfunction "2_2") (pintype "passive"))
      (node (ref "U$5") (pin "10") (pinfunction "G0-A1.0-32K_XP_10") (pintype "bidirectional"))
    )
    (net (code "49") (name "/VBUS") (class "Default")
      (node (ref "AC1") (pin "7") (pinfunction "VCC_7") (pintype "power_in"))
      (node (ref "C13") (pin "1") (pinfunction "1_1") (pintype "passive"))
      (node (ref "D5") (pin "2") (pinfunction "A_2") (pintype "bidirectional"))
      (node (ref "J1") (pin "A4/B9") (pinfunction "VBUS_A4/B9") (pintype "power_in"))
      (node (ref "J1") (pin "B4/A9") (pinfunction "VBUS_B4/A9") (pintype "power_in"))
      (node (ref "JP17") (pin "4") (pinfunction "4_4") (pintype "passive"))
    )
    (net (code "50") (name "/WET_MEAS") (class "Default")
      (node (ref "IC1") (pin "17") (pinfunction "P1_7_17") (pintype "bidirectional"))
      (node (ref "R15") (pin "2") (pinfunction "2_2") (pintype "passive"))
      (node (ref "T1") (pin "C") (pinfunction "C_C") (pintype "passive"))
    )
    (net (code "51") (name "AGND") (class "Default")
      (node (ref "U$1") (pin "P$1") (pinfunction "G1_P$1") (pintype "bidirectional"))
      (node (ref "U$1") (pin "P$2") (pinfunction "G2_P$2") (pintype "bidirectional"))
      (node (ref "U$1") (pin "P$3") (pinfunction "G3_P$3") (pintype "bidirectional"))
      (node (ref "U$1") (pin "P$4") (pinfunction "G4_P$4") (pintype "bidirectional"))
      (node (ref "U$7") (pin "P$1") (pinfunction "P$1_P$1") (pintype "bidirectional"))
    )
    (net (code "52") (name "GND") (class "Default")
      (node (ref "AC1") (pin "11") (pinfunction "EPAD_11") (pintype "power_in"))
      (node (ref "AC1") (pin "3") (pinfunction "GND_3") (pintype "power_in"))
      (node (ref "C11") (pin "1") (pinfunction "1_1") (pintype "passive"))
      (node (ref "C12") (pin "2") (pinfunction "2_2") (pintype "passive"))
      (node (ref "C13") (pin "2") (pinfunction "2_2") (pintype "passive"))
      (node (ref "C16") (pin "2") (pinfunction "2_2") (pintype "passive"))
      (node (ref "C2") (pin "2") (pinfunction "2_2") (pintype "passive"))
      (node (ref "C3") (pin "2") (pinfunction "2_2") (pintype "passive"))
      (node (ref "C4") (pin "2") (pinfunction "2_2") (pintype "passive"))
      (node (ref "C5") (pin "2") (pinfunction "2_2") (pintype "passive"))
      (node (ref "C6") (pin "2") (pinfunction "2_2") (pintype "passive"))
      (node (ref "C7") (pin "2") (pinfunction "2_2") (pintype "passive"))
      (node (ref "C8") (pin "2") (pinfunction "2_2") (pintype "passive"))
      (node (ref "C9") (pin "1") (pinfunction "1_1") (pintype "passive"))
      (node (ref "D1") (pin "1") (pinfunction "1_1") (pintype "bidirectional"))
      (node (ref "D4") (pin "1") (pinfunction "1_1") (pintype "bidirectional"))
      (node (ref "D6") (pin "2") (pinfunction "GND_2") (pintype "bidirectional"))
      (node (ref "D6") (pin "4") (pinfunction "GND_4") (pintype "bidirectional"))
      (node (ref "D6") (pin "5") (pinfunction "GND_5") (pintype "bidirectional"))
      (node (ref "D8") (pin "2") (pinfunction "GND_2") (pintype "bidirectional"))
      (node (ref "D8") (pin "4") (pinfunction "GND_4") (pintype "bidirectional"))
      (node (ref "D8") (pin "5") (pinfunction "GND_5") (pintype "bidirectional"))
      (node (ref "IC1") (pin "18") (pinfunction "AD0_18") (pintype "bidirectional"))
      (node (ref "IC1") (pin "24") (pinfunction "AD1_24") (pintype "bidirectional"))
      (node (ref "IC1") (pin "25") (pinfunction "GND_2_25") (pintype "bidirectional"))
      (node (ref "IC1") (pin "9") (pinfunction "GND_1_9") (pintype "bidirectional"))
      (node (ref "IC2") (pin "1") (pinfunction "GND_1") (pintype "bidirectional"))
      (node (ref "IC6") (pin "6") (pinfunction "~{E}_6") (pintype "bidirectional"))
      (node (ref "IC6") (pin "7") (pinfunction "VEE_7") (pintype "bidirectional"))
      (node (ref "IC6") (pin "8") (pinfunction "GND_8") (pintype "bidirectional"))
      (node (ref "J1") (pin "A1/B12") (pinfunction "GND_A1/B12") (pintype "power_in"))
      (node (ref "J1") (pin "B1/A12") (pinfunction "GND_B1/A12") (pintype "power_in"))
      (node (ref "J1") (pin "S1") (pinfunction "SHIELD_S1") (pintype "passive"))
      (node (ref "J1") (pin "S2") (pinfunction "SHIELD_S2") (pintype "passive"))
      (node (ref "J1") (pin "S3") (pinfunction "SHIELD_S3") (pintype "passive"))
      (node (ref "J1") (pin "S4") (pinfunction "SHIELD_S4") (pintype "passive"))
      (node (ref "JP1") (pin "3") (pinfunction "3_3") (pintype "passive"))
      (node (ref "JP17") (pin "1") (pinfunction "1_1") (pintype "passive"))
      (node (ref "JP2") (pin "3") (pinfunction "3_3") (pintype "passive"))
      (node (ref "JP5") (pin "4") (pinfunction "4_4") (pintype "passive"))
      (node (ref "JP9") (pin "4") (pinfunction "4_4") (pintype "passive"))
      (node (ref "Q1") (pin "2") (pinfunction "S_2") (pintype "passive"))
      (node (ref "R12") (pin "1") (pinfunction "1_1") (pintype "passive"))
      (node (ref "R20") (pin "2") (pinfunction "2_2") (pintype "passive"))
      (node (ref "R22") (pin "2") (pinfunction "2_2") (pintype "passive"))
      (node (ref "R5") (pin "1") (pinfunction "1_1") (pintype "passive"))
      (node (ref "R6") (pin "1") (pinfunction "1_1") (pintype "passive"))
      (node (ref "R9") (pin "2") (pinfunction "2_2") (pintype "passive"))
      (node (ref "S1") (pin "C1") (pinfunction "NO_1_C1") (pintype "bidirectional"))
      (node (ref "S1") (pin "D1") (pinfunction "NO_2_D1") (pintype "bidirectional"))
      (node (ref "S2") (pin "C1") (pinfunction "NO_1_C1") (pintype "bidirectional"))
      (node (ref "S2") (pin "D1") (pinfunction "NO_2_D1") (pintype "bidirectional"))
      (node (ref "T1") (pin "E") (pinfunction "E_E") (pintype "passive"))
      (node (ref "U$5") (pin "13") (pinfunction "GND2_13") (pintype "bidirectional"))
      (node (ref "U$5") (pin "2") (pinfunction "GND1_2") (pintype "bidirectional"))
      (node (ref "U$5") (pin "21") (pinfunction "GND3_21") (pintype "bidirectional"))
      (node (ref "U$7") (pin "P$2") (pinfunction "P$2_P$2") (pintype "bidirectional"))
    )
    (net (code "53") (name "Net-(AC1-V3)") (class "Default")
      (node (ref "AC1") (pin "10") (pinfunction "V3_10") (pintype "power_in"))
      (node (ref "C9") (pin "2") (pinfunction "2_2") (pintype "passive"))
    )
    (net (code "54") (name "Net-(C1-Pad1)") (class "Default")
      (node (ref "C1") (pin "1") (pinfunction "1_1") (pintype "passive"))
      (node (ref "JP13") (pin "1") (pinfunction "1_1") (pintype "passive"))
      (node (ref "R4") (pin "2") (pinfunction "2_2") (pintype "passive"))
    )
    (net (code "55") (name "Net-(C1-Pad2)") (class "Default")
      (node (ref "C1") (pin "2") (pinfunction "2_2") (pintype "passive"))
      (node (ref "JP14") (pin "1") (pinfunction "1_1") (pintype "passive"))
      (node (ref "R22") (pin "1") (pinfunction "1_1") (pintype "passive"))
      (node (ref "T1") (pin "B") (pinfunction "B_B") (pintype "passive"))
    )
    (net (code "56") (name "Net-(D2-A)") (class "Default")
      (node (ref "D2") (pin "2") (pinfunction "A_2") (pintype "bidirectional"))
      (node (ref "IC4") (pin "2") (pinfunction "K_2") (pintype "bidirectional"))
    )
    (net (code "57") (name "Net-(D2-K)") (class "Default")
      (node (ref "D2") (pin "1") (pinfunction "K_1") (pintype "bidirectional"))
      (node (ref "R16") (pin "2") (pinfunction "2_2") (pintype "passive"))
    )
    (net (code "58") (name "Net-(IC3-A)") (class "Default")
      (node (ref "IC3") (pin "1") (pinfunction "A_1") (pintype "bidirectional"))
      (node (ref "R26") (pin "1") (pinfunction "1_1") (pintype "passive"))
    )
    (net (code "59") (name "Net-(IC3-E)") (class "Default")
      (node (ref "IC3") (pin "3") (pinfunction "E_3") (pintype "bidirectional"))
      (node (ref "R14") (pin "1") (pinfunction "1_1") (pintype "passive"))
      (node (ref "R8") (pin "2") (pinfunction "2_2") (pintype "passive"))
    )
    (net (code "60") (name "Net-(IC3-K)") (class "Default")
      (node (ref "IC3") (pin "2") (pinfunction "K_2") (pintype "bidirectional"))
      (node (ref "IC5") (pin "2") (pinfunction "K_2") (pintype "bidirectional"))
      (node (ref "Q1") (pin "3") (pinfunction "D_3") (pintype "passive"))
    )
    (net (code "61") (name "Net-(IC4-A)") (class "Default")
      (node (ref "IC4") (pin "1") (pinfunction "A_1") (pintype "bidirectional"))
      (node (ref "R17") (pin "2") (pinfunction "2_2") (pintype "passive"))
    )
    (net (code "62") (name "Net-(IC5-A)") (class "Default")
      (node (ref "IC5") (pin "1") (pinfunction "A_1") (pintype "bidirectional"))
      (node (ref "R25") (pin "1") (pinfunction "1_1") (pintype "passive"))
    )
    (net (code "63") (name "Net-(IC5-E)") (class "Default")
      (node (ref "IC5") (pin "3") (pinfunction "E_3") (pintype "bidirectional"))
      (node (ref "R7") (pin "2") (pinfunction "2_2") (pintype "passive"))
      (node (ref "R9") (pin "1") (pinfunction "1_1") (pintype "passive"))
    )
    (net (code "64") (name "Net-(J1-CC1)") (class "Default")
      (node (ref "J1") (pin "A5") (pinfunction "CC1_A5") (pintype "bidirectional"))
      (node (ref "R5") (pin "2") (pinfunction "2_2") (pintype "passive"))
    )
    (net (code "65") (name "Net-(J1-CC2)") (class "Default")
      (node (ref "J1") (pin "B5") (pinfunction "CC2_B5") (pintype "bidirectional"))
      (node (ref "R6") (pin "2") (pinfunction "2_2") (pintype "passive"))
    )
    (net (code "66") (name "Net-(JP5-Pad1)") (class "Default")
      (node (ref "JP5") (pin "1") (pinfunction "1_1") (pintype "passive"))
      (node (ref "JP7") (pin "2") (pinfunction "2_2") (pintype "passive"))
      (node (ref "R35") (pin "1") (pinfunction "1_1") (pintype "passive"))
      (node (ref "R37") (pin "1") (pinfunction "1_1") (pintype "passive"))
    )
    (net (code "67") (name "Net-(JP6-Pad1)") (class "Default")
      (node (ref "JP6") (pin "1") (pinfunction "1_1") (pintype "passive"))
      (node (ref "R1") (pin "2") (pinfunction "2_2") (pintype "passive"))
    )
    (net (code "68") (name "Net-(JP10-Pad2)") (class "Default")
      (node (ref "JP10") (pin "2") (pinfunction "2_2") (pintype "passive"))
      (node (ref "JP9") (pin "1") (pinfunction "1_1") (pintype "passive"))
      (node (ref "R31") (pin "1") (pinfunction "1_1") (pintype "passive"))
      (node (ref "R33") (pin "1") (pinfunction "1_1") (pintype "passive"))
    )
    (net (code "69") (name "Net-(LED2-PadA)") (class "Default")
      (node (ref "LED2") (pin "A") (pinfunction "A_A") (pintype "passive"))
      (node (ref "R41") (pin "2") (pinfunction "2_2") (pintype "passive"))
    )
    (net (code "70") (name "Net-(LED3-PadA)") (class "Default")
      (node (ref "LED3") (pin "A") (pinfunction "A_A") (pintype "passive"))
      (node (ref "R42") (pin "2") (pinfunction "2_2") (pintype "passive"))
    )
    (net (code "71") (name "Net-(L_ANT1-Pad1)") (class "Default")
      (node (ref "L_ANT1") (pin "1") (pinfunction "1_1") (pintype "passive"))
      (node (ref "R_ANT") (pin "2") (pinfunction "2_2") (pintype "passive"))
    )
    (net (code "72") (name "Net-(L_ANT1-Pad2)") (class "Default")
      (node (ref "L_ANT1") (pin "2") (pinfunction "2_2") (pintype "passive"))
      (node (ref "R2") (pin "2") (pinfunction "2_2") (pintype "passive"))
    )
    (net (code "73") (name "Net-(R13-Pad2)") (class "Default")
      (node (ref "R13") (pin "2") (pinfunction "2_2") (pintype "passive"))
      (node (ref "R16") (pin "1") (pinfunction "1_1") (pintype "passive"))
    )
    (net (code "74") (name "Net-(R17-Pad1)") (class "Default")
      (node (ref "R17") (pin "1") (pinfunction "1_1") (pintype "passive"))
      (node (ref "R18") (pin "2") (pinfunction "2_2") (pintype "passive"))
    )
    (net (code "75") (name "Net-(U$5-2G4_ANT)") (class "Default")
      (node (ref "R_ANT") (pin "1") (pinfunction "1_1") (pintype "passive"))
      (node (ref "U$5") (pin "1") (pinfunction "2G4_ANT_1") (pintype "bidirectional"))
    )
    (net (code "76") (name "V+") (class "Default")
      (node (ref "C12") (pin "1") (pinfunction "1_1") (pintype "passive"))
      (node (ref "C3") (pin "1") (pinfunction "1_1") (pintype "passive"))
      (node (ref "C4") (pin "1") (pinfunction "1_1") (pintype "passive"))
      (node (ref "C6") (pin "1") (pinfunction "1_1") (pintype "passive"))
      (node (ref "C7") (pin "1") (pinfunction "1_1") (pintype "passive"))
      (node (ref "C8") (pin "1") (pinfunction "1_1") (pintype "passive"))
      (node (ref "IC1") (pin "21") (pinfunction "VCC_21") (pintype "bidirectional"))
      (node (ref "IC1") (pin "23") (pinfunction "RSTN_23") (pintype "bidirectional"))
      (node (ref "IC2") (pin "2") (pinfunction "VOUT_1_2") (pintype "bidirectional"))
      (node (ref "IC2") (pin "4") (pinfunction "VOUT_2_4") (pintype "bidirectional"))
      (node (ref "IC6") (pin "16") (pinfunction "VCC_16") (pintype "bidirectional"))
      (node (ref "JP10") (pin "1") (pinfunction "1_1") (pintype "passive"))
      (node (ref "JP7") (pin "1") (pinfunction "1_1") (pintype "passive"))
      (node (ref "Q2") (pin "1") (pinfunction "G_1") (pintype "passive"))
      (node (ref "Q5") (pin "1") (pinfunction "G_1") (pintype "passive"))
      (node (ref "Q6") (pin "1") (pinfunction "G_1") (pintype "passive"))
      (node (ref "Q7") (pin "1") (pinfunction "G_1") (pintype "passive"))
      (node (ref "R10") (pin "1") (pinfunction "1_1") (pintype "passive"))
      (node (ref "R11") (pin "1") (pinfunction "1_1") (pintype "passive"))
      (node (ref "R24") (pin "1") (pinfunction "1_1") (pintype "passive"))
      (node (ref "R28") (pin "1") (pinfunction "1_1") (pintype "passive"))
      (node (ref "R30") (pin "1") (pinfunction "1_1") (pintype "passive"))
      (node (ref "R32") (pin "1") (pinfunction "1_1") (pintype "passive"))
      (node (ref "R34") (pin "1") (pinfunction "1_1") (pintype "passive"))
      (node (ref "R36") (pin "1") (pinfunction "1_1") (pintype "passive"))
      (node (ref "R39") (pin "2") (pinfunction "2_2") (pintype "passive"))
      (node (ref "R40") (pin "2") (pinfunction "2_2") (pintype "passive"))
      (node (ref "R41") (pin "1") (pinfunction "1_1") (pintype "passive"))
      (node (ref "R42") (pin "1") (pinfunction "1_1") (pintype "passive"))
      (node (ref "U$5") (pin "12") (pinfunction "VDD_12") (pintype "bidirectional"))
    )
    (net (code "77") (name "unconnected-(AC1-~{CTS}-Pad5)") (class "Default")
      (node (ref "AC1") (pin "5") (pinfunction "~{CTS}_5") (pintype "bidirectional"))
    )
    (net (code "78") (name "unconnected-(IC1-INTN-Pad22)") (class "Default")
      (node (ref "IC1") (pin "22") (pinfunction "INTN_22") (pintype "bidirectional"))
    )
    (net (code "79") (name "unconnected-(IC1-P0_2-Pad7)") (class "Default")
      (node (ref "IC1") (pin "7") (pinfunction "P0_2_7") (pintype "bidirectional"))
    )
    (net (code "80") (name "unconnected-(IC1-P0_3-Pad8)") (class "Default")
      (node (ref "IC1") (pin "8") (pinfunction "P0_3_8") (pintype "bidirectional"))
    )
    (net (code "81") (name "unconnected-(IC1-P0_5-Pad11)") (class "Default")
      (node (ref "IC1") (pin "11") (pinfunction "P0_5_11") (pintype "bidirectional"))
    )
    (net (code "82") (name "unconnected-(IC1-P0_6-Pad12)") (class "Default")
      (node (ref "IC1") (pin "12") (pinfunction "P0_6_12") (pintype "bidirectional"))
    )
    (net (code "83") (name "unconnected-(J1-SBU1-PadA8)") (class "Default")
      (node (ref "J1") (pin "A8") (pinfunction "SBU1_A8") (pintype "bidirectional"))
    )
    (net (code "84") (name "unconnected-(J1-SBU2-PadB8)") (class "Default")
      (node (ref "J1") (pin "B8") (pinfunction "SBU2_B8") (pintype "bidirectional"))
    )
    (net (code "85") (name "unconnected-(JP2-Pad1)") (class "Default")
      (node (ref "JP2") (pin "1") (pinfunction "1_1") (pintype "passive"))
    )
    (net (code "86") (name "unconnected-(JP3-Pad1)") (class "Default")
      (node (ref "JP3") (pin "1") (pinfunction "1_1") (pintype "passive"))
    )
    (net (code "87") (name "unconnected-(R2-Pad1)") (class "Default")
      (node (ref "R2") (pin "1") (pinfunction "1_1") (pintype "passive"))
    )
    (net (code "88") (name "unconnected-(U$5-FSPICS0-LO_SCK-G10-Pad14)") (class "Default")
      (node (ref "U$5") (pin "14") (pinfunction "FSPICS0-LO_SCK-G10_14") (pintype "bidirectional"))
    )
    (net (code "89") (name "unconnected-(U$5-G3-A1.3-LORA_DIO1-Pad7)") (class "Default")
      (node (ref "U$5") (pin "7") (pinfunction "G3-A1.3-LORA_DIO1_7") (pintype "bidirectional"))
    )
    (net (code "90") (name "unconnected-(U$5-G4-A1.4-LO_BY-MTMS-FSPIHD-Pad6)") (class "Default")
      (node (ref "U$5") (pin "6") (pinfunction "G4-A1.4-LO_BY-MTMS-FSPIHD_6") (pintype "bidirectional"))
    )
    (net (code "91") (name "unconnected-(U$5-G5-A2.0-LO_RST-MTDI-FSPIWP-Pad5)") (class "Default")
      (node (ref "U$5") (pin "5") (pinfunction "G5-A2.0-LO_RST-MTDI-FSPIWP_5") (pintype "bidirectional"))
    )
    (net (code "92") (name "unconnected-(U$5-G6-LO_MI-MTCK-FSPICK-Pad4)") (class "Default")
      (node (ref "U$5") (pin "4") (pinfunction "G6-LO_MI-MTCK-FSPICK_4") (pintype "bidirectional"))
    )
    (net (code "93") (name "unconnected-(U$5-G7-LO_MO-MTDO-FSPID-Pad3)") (class "Default")
      (node (ref "U$5") (pin "3") (pinfunction "G7-LO_MO-MTDO-FSPID_3") (pintype "bidirectional"))
    )
    (net (code "94") (name "unconnected-(U$5-LO_NSS-G8-Pad16)") (class "Default")
      (node (ref "U$5") (pin "16") (pinfunction "LO_NSS-G8_16") (pintype "bidirectional"))
    )
  )
)
